# tranwithatmega1_0.net
KiCad netlist of a schematic drawn in EAGLE
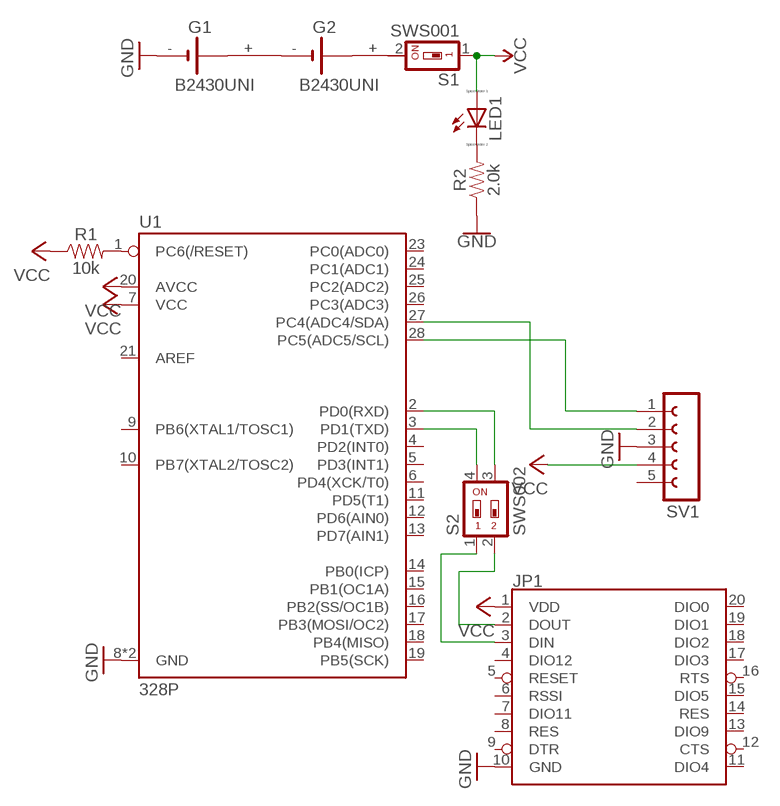
[diagram p0: schematic, sheet 1]

(export (version "E")
  (design (tool "Eeschema 10.0.6"))
  (components
    (comp (ref "G1")
      (value "B2430UNI")
      (footprint "eagle-import:B2430UNI")
      (libsource (lib "eagle-import") (part "B2430UNI"))
    )
    (comp (ref "G2")
      (value "B2430UNI")
      (footprint "eagle-import:B2430UNI")
      (libsource (lib "eagle-import") (part "B2430UNI"))
    )
    (comp (ref "JP1")
      (value "XBEE")
      (footprint "eagle-import:XBEE")
      (libsource (lib "eagle-import") (part "XBEE"))
    )
    (comp (ref "LED1")
      (value "LED_E")
      (footprint "eagle-import:LED_1206")
      (libsource (lib "eagle-import") (part "LED_E"))
    )
    (comp (ref "R1")
      (value "10k")
      (footprint "eagle-import:AXIAL-0.3")
      (libsource (lib "eagle-import") (part "10KOHM-HORIZ-1/4W-1%"))
    )
    (comp (ref "R2")
      (value "2.0k")
      (footprint "eagle-import:0603")
      (libsource (lib "eagle-import") (part "2.0KOHM-0603-1/10W-5%"))
    )
    (comp (ref "S1")
      (value "SWS001")
      (footprint "eagle-import:SMS-001")
      (libsource (lib "eagle-import") (part "SWS001"))
    )
    (comp (ref "S2")
      (value "SWS002")
      (footprint "eagle-import:SMS-002")
      (libsource (lib "eagle-import") (part "SWS002"))
    )
    (comp (ref "SV1")
      (value "FE05-1")
      (footprint "eagle-import:FE05-1")
      (libsource (lib "eagle-import") (part "FE05-1"))
    )
    (comp (ref "U1")
      (value "328P")
      (footprint "eagle-import:DIP28")
      (libsource (lib "eagle-import") (part "ATMEGA328P_PDIP"))
    )
  )
  (nets
    (net (code "1") (name "GND") (class "Default")
      (node (ref "G1") (pin "-") (pinfunction "-_-") (pintype "passive"))
      (node (ref "JP1") (pin "10") (pinfunction "GND_10") (pintype "power_in"))
      (node (ref "R2") (pin "1") (pinfunction "1_1") (pintype "passive"))
      (node (ref "SV1") (pin "3") (pinfunction "3_3") (pintype "passive"))
      (node (ref "U1") (pin "22") (pinfunction "GND_22") (pintype "bidirectional"))
      (node (ref "U1") (pin "8") (pinfunction "GND_8") (pintype "bidirectional"))
    )
    (net (code "2") (name "Net-(G1-Pad+)") (class "Default")
      (node (ref "G1") (pin "+") (pinfunction "+_+") (pintype "passive"))
      (node (ref "G2") (pin "-") (pinfunction "-_-") (pintype "passive"))
    )
    (net (code "3") (name "Net-(G2-+-Pad+@1)") (class "Default")
      (node (ref "G2") (pin "+@1") (pinfunction "+_+@1") (pintype "passive"))
      (node (ref "S1") (pin "2") (pinfunction "2_2") (pintype "passive"))
    )
    (net (code "4") (name "Net-(JP1-DIN)") (class "Default")
      (node (ref "JP1") (pin "3") (pinfunction "DIN_3") (pintype "input"))
      (node (ref "S2") (pin "1") (pinfunction "1_1") (pintype "passive"))
    )
    (net (code "5") (name "Net-(JP1-DOUT)") (class "Default")
      (node (ref "JP1") (pin "2") (pinfunction "DOUT_2") (pintype "output"))
      (node (ref "S2") (pin "2") (pinfunction "2_2") (pintype "passive"))
    )
    (net (code "6") (name "Net-(LED1-PadC)") (class "Default")
      (node (ref "LED1") (pin "C") (pinfunction "C_C") (pintype "passive"))
      (node (ref "R2") (pin "2") (pinfunction "2_2") (pintype "passive"))
    )
    (net (code "7") (name "Net-(R1-2)") (class "Default")
      (node (ref "R1") (pin "P$2") (pinfunction "2_P$2") (pintype "passive"))
      (node (ref "U1") (pin "1") (pinfunction "PC6(/RESET)_1") (pintype "bidirectional"))
    )
    (net (code "8") (name "Net-(U1-PC4(ADC4{slash}SDA))") (class "Default")
      (node (ref "SV1") (pin "2") (pinfunction "2_2") (pintype "passive"))
      (node (ref "U1") (pin "27") (pinfunction "PC4(ADC4/SDA)_27") (pintype "bidirectional"))
    )
    (net (code "9") (name "Net-(U1-PC5(ADC5{slash}SCL))") (class "Default")
      (node (ref "SV1") (pin "1") (pinfunction "1_1") (pintype "passive"))
      (node (ref "U1") (pin "28") (pinfunction "PC5(ADC5/SCL)_28") (pintype "bidirectional"))
    )
    (net (code "10") (name "Net-(U1-PD0(RXD))") (class "Default")
      (node (ref "S2") (pin "3") (pinfunction "3_3") (pintype "passive"))
      (node (ref "U1") (pin "2") (pinfunction "PD0(RXD)_2") (pintype "bidirectional"))
    )
    (net (code "11") (name "Net-(U1-PD1(TXD))") (class "Default")
      (node (ref "S2") (pin "4") (pinfunction "4_4") (pintype "passive"))
      (node (ref "U1") (pin "3") (pinfunction "PD1(TXD)_3") (pintype "bidirectional"))
    )
    (net (code "12") (name "VCC") (class "Default")
      (node (ref "JP1") (pin "1") (pinfunction "VDD_1") (pintype "power_in"))
      (node (ref "LED1") (pin "A") (pinfunction "A_A") (pintype "passive"))
      (node (ref "R1") (pin "P$1") (pinfunction "1_P$1") (pintype "passive"))
      (node (ref "S1") (pin "1") (pinfunction "1_1") (pintype "passive"))
      (node (ref "SV1") (pin "4") (pinfunction "4_4") (pintype "passive"))
      (node (ref "U1") (pin "20") (pinfunction "AVCC_20") (pintype "bidirectional"))
      (node (ref "U1") (pin "7") (pinfunction "VCC_7") (pintype "bidirectional"))
    )
    (net (code "13") (name "unconnected-(G1-+-Pad+@1)") (class "Default")
      (node (ref "G1") (pin "+@1") (pinfunction "+_+@1") (pintype "passive"))
    )
    (net (code "14") (name "unconnected-(G1-+-Pad+@2)") (class "Default")
      (node (ref "G1") (pin "+@2") (pinfunction "+_+@2") (pintype "passive"))
    )
    (net (code "15") (name "unconnected-(G1-+-Pad+@3)") (class "Default")
      (node (ref "G1") (pin "+@3") (pinfunction "+_+@3") (pintype "passive"))
    )
    (net (code "16") (name "unconnected-(G1-+-Pad+@4)") (class "Default")
      (node (ref "G1") (pin "+@4") (pinfunction "+_+@4") (pintype "passive"))
    )
    (net (code "17") (name "unconnected-(G1---Pad-@1)") (class "Default")
      (node (ref "G1") (pin "-@1") (pinfunction "-_-@1") (pintype "passive"))
    )
    (net (code "18") (name "unconnected-(G2-+-Pad+@2)") (class "Default")
      (node (ref "G2") (pin "+@2") (pinfunction "+_+@2") (pintype "passive"))
    )
    (net (code "19") (name "unconnected-(G2-+-Pad+@3)") (class "Default")
      (node (ref "G2") (pin "+@3") (pinfunction "+_+@3") (pintype "passive"))
    )
    (net (code "20") (name "unconnected-(G2-+-Pad+@4)") (class "Default")
      (node (ref "G2") (pin "+@4") (pinfunction "+_+@4") (pintype "passive"))
    )
    (net (code "21") (name "unconnected-(G2---Pad-@1)") (class "Default")
      (node (ref "G2") (pin "-@1") (pinfunction "-_-@1") (pintype "passive"))
    )
    (net (code "22") (name "unconnected-(G2-Pad+)") (class "Default")
      (node (ref "G2") (pin "+") (pinfunction "+_+") (pintype "passive"))
    )
    (net (code "23") (name "unconnected-(JP1-CTS-Pad12)") (class "Default")
      (node (ref "JP1") (pin "12") (pinfunction "CTS_12") (pintype "output"))
    )
    (net (code "24") (name "unconnected-(JP1-DIO0-Pad20)") (class "Default")
      (node (ref "JP1") (pin "20") (pinfunction "DIO0_20") (pintype "bidirectional"))
    )
    (net (code "25") (name "unconnected-(JP1-DIO1-Pad19)") (class "Default")
      (node (ref "JP1") (pin "19") (pinfunction "DIO1_19") (pintype "bidirectional"))
    )
    (net (code "26") (name "unconnected-(JP1-DIO2-Pad18)") (class "Default")
      (node (ref "JP1") (pin "18") (pinfunction "DIO2_18") (pintype "bidirectional"))
    )
    (net (code "27") (name "unconnected-(JP1-DIO3-Pad17)") (class "Default")
      (node (ref "JP1") (pin "17") (pinfunction "DIO3_17") (pintype "bidirectional"))
    )
    (net (code "28") (name "unconnected-(JP1-DIO4-Pad11)") (class "Default")
      (node (ref "JP1") (pin "11") (pinfunction "DIO4_11") (pintype "bidirectional"))
    )
    (net (code "29") (name "unconnected-(JP1-DIO5-Pad15)") (class "Default")
      (node (ref "JP1") (pin "15") (pinfunction "DIO5_15") (pintype "bidirectional"))
    )
    (net (code "30") (name "unconnected-(JP1-DIO9-Pad13)") (class "Default")
      (node (ref "JP1") (pin "13") (pinfunction "DIO9_13") (pintype "bidirectional"))
    )
    (net (code "31") (name "unconnected-(JP1-DIO11-Pad7)") (class "Default")
      (node (ref "JP1") (pin "7") (pinfunction "DIO11_7") (pintype "bidirectional"))
    )
    (net (code "32") (name "unconnected-(JP1-DIO12-Pad4)") (class "Default")
      (node (ref "JP1") (pin "4") (pinfunction "DIO12_4") (pintype "bidirectional"))
    )
    (net (code "33") (name "unconnected-(JP1-DTR-Pad9)") (class "Default")
      (node (ref "JP1") (pin "9") (pinfunction "DTR_9") (pintype "bidirectional"))
    )
    (net (code "34") (name "unconnected-(JP1-RES-Pad8)") (class "Default")
      (node (ref "JP1") (pin "8") (pinfunction "RES_8") (pintype "bidirectional"))
    )
    (net (code "35") (name "unconnected-(JP1-RES-Pad14)") (class "Default")
      (node (ref "JP1") (pin "14") (pinfunction "RES_14") (pintype "bidirectional"))
    )
    (net (code "36") (name "unconnected-(JP1-RESET-Pad5)") (class "Default")
      (node (ref "JP1") (pin "5") (pinfunction "RESET_5") (pintype "input"))
    )
    (net (code "37") (name "unconnected-(JP1-RSSI-Pad6)") (class "Default")
      (node (ref "JP1") (pin "6") (pinfunction "RSSI_6") (pintype "bidirectional"))
    )
    (net (code "38") (name "unconnected-(JP1-RTS-Pad16)") (class "Default")
      (node (ref "JP1") (pin "16") (pinfunction "RTS_16") (pintype "input"))
    )
    (net (code "39") (name "unconnected-(SV1-Pad5)") (class "Default")
      (node (ref "SV1") (pin "5") (pinfunction "5_5") (pintype "passive"))
    )
    (net (code "40") (name "unconnected-(U1-AREF-Pad21)") (class "Default")
      (node (ref "U1") (pin "21") (pinfunction "AREF_21") (pintype "bidirectional"))
    )
    (net (code "41") (name "unconnected-(U1-PB0(ICP)-Pad14)") (class "Default")
      (node (ref "U1") (pin "14") (pinfunction "PB0(ICP)_14") (pintype "bidirectional"))
    )
    (net (code "42") (name "unconnected-(U1-PB1(OC1A)-Pad15)") (class "Default")
      (node (ref "U1") (pin "15") (pinfunction "PB1(OC1A)_15") (pintype "bidirectional"))
    )
    (net (code "43") (name "unconnected-(U1-PB2(SS{slash}OC1B)-Pad16)") (class "Default")
      (node (ref "U1") (pin "16") (pinfunction "PB2(SS/OC1B)_16") (pintype "bidirectional"))
    )
    (net (code "44") (name "unconnected-(U1-PB3(MOSI{slash}OC2)-Pad17)") (class "Default")
      (node (ref "U1") (pin "17") (pinfunction "PB3(MOSI/OC2)_17") (pintype "bidirectional"))
    )
    (net (code "45") (name "unconnected-(U1-PB4(MISO)-Pad18)") (class "Default")
      (node (ref "U1") (pin "18") (pinfunction "PB4(MISO)_18") (pintype "bidirectional"))
    )
    (net (code "46") (name "unconnected-(U1-PB5(SCK)-Pad19)") (class "Default")
      (node (ref "U1") (pin "19") (pinfunction "PB5(SCK)_19") (pintype "bidirectional"))
    )
    (net (code "47") (name "unconnected-(U1-PB6(XTAL1{slash}TOSC1)-Pad9)") (class "Default")
      (node (ref "U1") (pin "9") (pinfunction "PB6(XTAL1/TOSC1)_9") (pintype "bidirectional"))
    )
    (net (code "48") (name "unconnected-(U1-PB7(XTAL2{slash}TOSC2)-Pad10)") (class "Default")
      (node (ref "U1") (pin "10") (pinfunction "PB7(XTAL2/TOSC2)_10") (pintype "bidirectional"))
    )
    (net (code "49") (name "unconnected-(U1-PC0(ADC0)-Pad23)") (class "Default")
      (node (ref "U1") (pin "23") (pinfunction "PC0(ADC0)_23") (pintype "bidirectional"))
    )
    (net (code "50") (name "unconnected-(U1-PC1(ADC1)-Pad24)") (class "Default")
      (node (ref "U1") (pin "24") (pinfunction "PC1(ADC1)_24") (pintype "bidirectional"))
    )
    (net (code "51") (name "unconnected-(U1-PC2(ADC2)-Pad25)") (class "Default")
      (node (ref "U1") (pin "25") (pinfunction "PC2(ADC2)_25") (pintype "bidirectional"))
    )
    (net (code "52") (name "unconnected-(U1-PC3(ADC3)-Pad26)") (class "Default")
      (node (ref "U1") (pin "26") (pinfunction "PC3(ADC3)_26") (pintype "bidirectional"))
    )
    (net (code "53") (name "unconnected-(U1-PD2(INT0)-Pad4)") (class "Default")
      (node (ref "U1") (pin "4") (pinfunction "PD2(INT0)_4") (pintype "bidirectional"))
    )
    (net (code "54") (name "unconnected-(U1-PD3(INT1)-Pad5)") (class "Default")
      (node (ref "U1") (pin "5") (pinfunction "PD3(INT1)_5") (pintype "bidirectional"))
    )
    (net (code "55") (name "unconnected-(U1-PD4(XCK{slash}T0)-Pad6)") (class "Default")
      (node (ref "U1") (pin "6") (pinfunction "PD4(XCK/T0)_6") (pintype "bidirectional"))
    )
    (net (code "56") (name "unconnected-(U1-PD5(T1)-Pad11)") (class "Default")
      (node (ref "U1") (pin "11") (pinfunction "PD5(T1)_11") (pintype "bidirectional"))
    )
    (net (code "57") (name "unconnected-(U1-PD6(AIN0)-Pad12)") (class "Default")
      (node (ref "U1") (pin "12") (pinfunction "PD6(AIN0)_12") (pintype "bidirectional"))
    )
    (net (code "58") (name "unconnected-(U1-PD7(AIN1)-Pad13)") (class "Default")
      (node (ref "U1") (pin "13") (pinfunction "PD7(AIN1)_13") (pintype "bidirectional"))
    )
  )
)
